# esp-breadboard.net
KiCad netlist of a schematic drawn in EAGLE
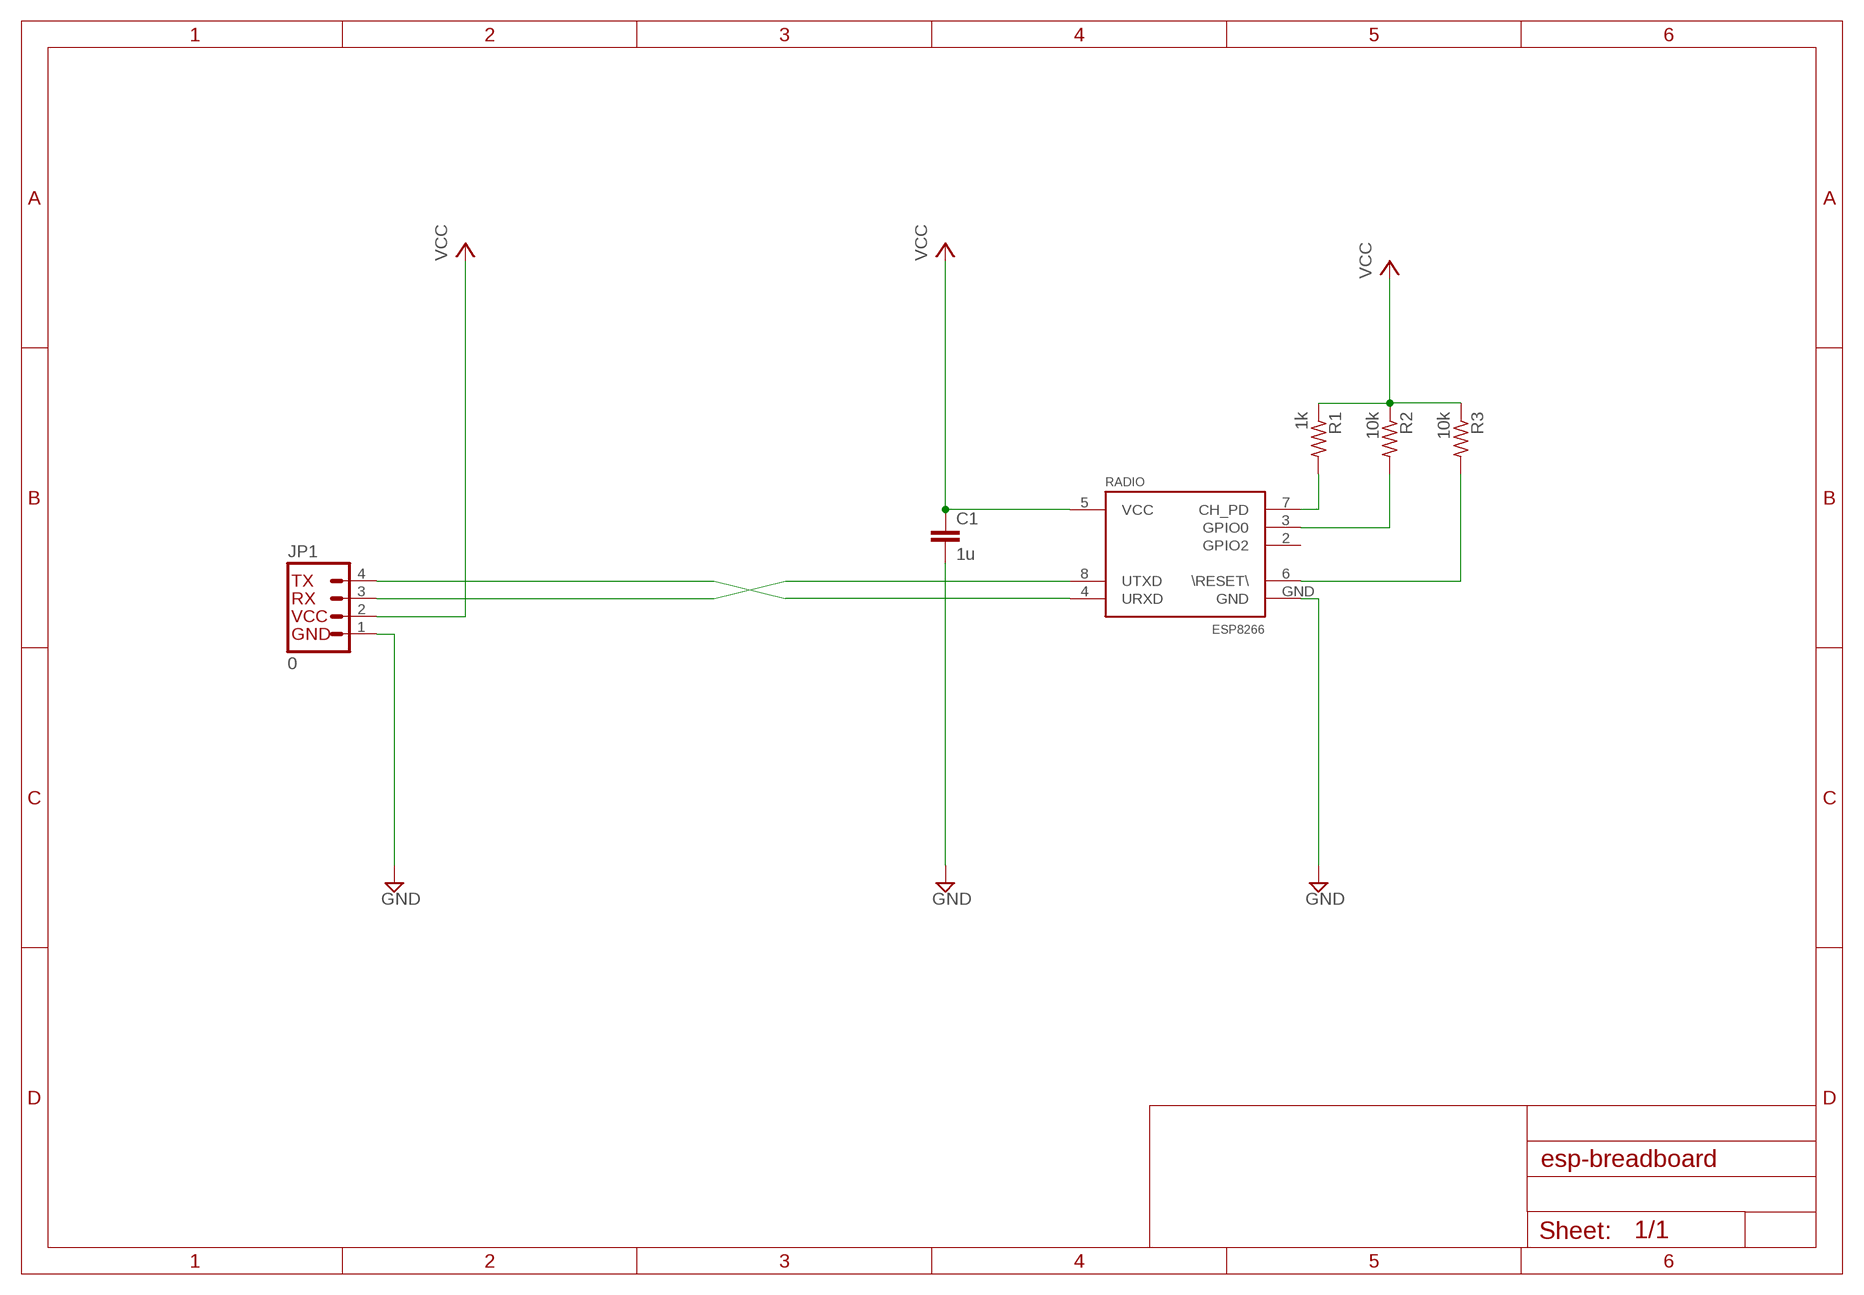
[diagram p0: schematic, sheet 1]

(export (version "E")
  (design (tool "Eeschema 10.0.6"))
  (components
    (comp (ref "C1")
      (value "1u")
      (footprint "eagle-import:C0805")
      (libsource (lib "eagle-import") (part "C-EUC0805"))
    )
    (comp (ref "JP1")
      (value "0")
      (footprint "eagle-import:1X04_NO_SILK")
      (libsource (lib "eagle-import") (part "I2C_STANDARD_NO_SILK"))
    )
    (comp (ref "R1")
      (value "1k")
      (footprint "eagle-import:R0805")
      (libsource (lib "eagle-import") (part "R-US_R0805"))
    )
    (comp (ref "R2")
      (value "10k")
      (footprint "eagle-import:R0805")
      (libsource (lib "eagle-import") (part "R-US_R0805"))
    )
    (comp (ref "R3")
      (value "10k")
      (footprint "eagle-import:R0805")
      (libsource (lib "eagle-import") (part "R-US_R0805"))
    )
    (comp (ref "RADIO")
      (value "ESP8266")
      (footprint "eagle-import:ESP8266-01")
      (libsource (lib "eagle-import") (part "ESP8266"))
    )
  )
  (nets
    (net (code "1") (name "GND") (class "Default")
      (node (ref "C1") (pin "2") (pinfunction "2_2") (pintype "passive"))
      (node (ref "JP1") (pin "1") (pinfunction "1_1") (pintype "passive"))
      (node (ref "RADIO") (pin "GND") (pinfunction "GND_GND") (pintype "power_in"))
    )
    (net (code "2") (name "Net-(RADIO-CH_PD)") (class "Default")
      (node (ref "R1") (pin "2") (pinfunction "2_2") (pintype "passive"))
      (node (ref "RADIO") (pin "7") (pinfunction "CH_PD_7") (pintype "bidirectional"))
    )
    (net (code "3") (name "Net-(RADIO-GPIO0)") (class "Default")
      (node (ref "R2") (pin "2") (pinfunction "2_2") (pintype "passive"))
      (node (ref "RADIO") (pin "3") (pinfunction "GPIO0_3") (pintype "bidirectional"))
    )
    (net (code "4") (name "Net-(RADIO-URXD)") (class "Default")
      (node (ref "JP1") (pin "4") (pinfunction "4_4") (pintype "passive"))
      (node (ref "RADIO") (pin "4") (pinfunction "URXD_4") (pintype "bidirectional"))
    )
    (net (code "5") (name "Net-(RADIO-UTXD)") (class "Default")
      (node (ref "JP1") (pin "3") (pinfunction "3_3") (pintype "passive"))
      (node (ref "RADIO") (pin "8") (pinfunction "UTXD_8") (pintype "bidirectional"))
    )
    (net (code "6") (name "Net-(RADIO-\\RESET\\)") (class "Default")
      (node (ref "R3") (pin "2") (pinfunction "2_2") (pintype "passive"))
      (node (ref "RADIO") (pin "6") (pinfunction "\\RESET\\_6") (pintype "bidirectional"))
    )
    (net (code "7") (name "VCC") (class "Default")
      (node (ref "C1") (pin "1") (pinfunction "1_1") (pintype "passive"))
      (node (ref "JP1") (pin "2") (pinfunction "2_2") (pintype "passive"))
      (node (ref "R1") (pin "1") (pinfunction "1_1") (pintype "passive"))
      (node (ref "R2") (pin "1") (pinfunction "1_1") (pintype "passive"))
      (node (ref "R3") (pin "1") (pinfunction "1_1") (pintype "passive"))
      (node (ref "RADIO") (pin "5") (pinfunction "VCC_5") (pintype "power_in"))
    )
    (net (code "8") (name "unconnected-(RADIO-GPIO2-Pad2)") (class "Default")
      (node (ref "RADIO") (pin "2") (pinfunction "GPIO2_2") (pintype "bidirectional"))
    )
  )
)
